# HC06_Schem.net
KiCad netlist of a schematic drawn in Altium Designer
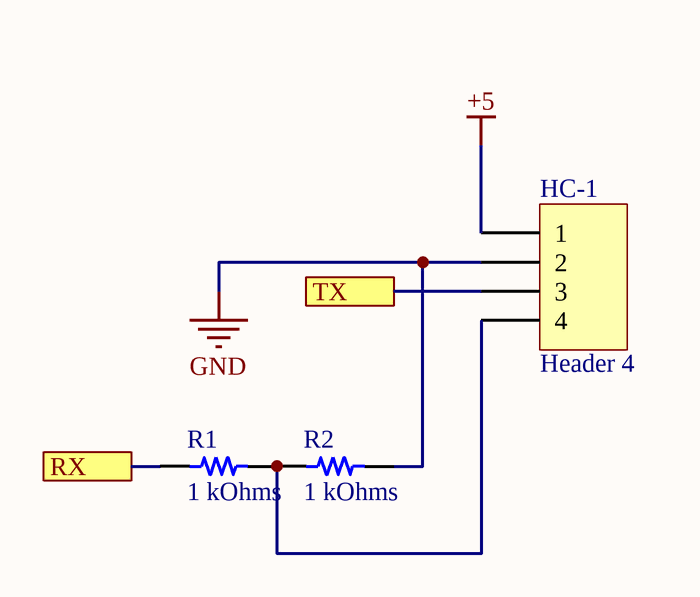
[diagram p0: HC06_Schem.SchDoc]

(export (version "E")
  (design (tool "Eeschema 10.0.6"))
  (components
    (comp (ref "HC-1")
      (value "Header 4")
      (footprint "HDR1X4")
      (description "Header, 4-Pin")
      (fields (field (name "PUBLISHER") "Altium Limited"))
      (libsource (lib "Miscellaneous Connectors") (part "Header 4"))
    )
    (comp (ref "R1")
      (value "1 kOhms")
      (footprint "RES 1210_3225")
      (description "RES SMD 1K OHM 5% 2/3W 1210")
      (fields (field (name "PART NUMBER") "ESR25JZPJ102") (field (name "MANUFACTURER") "Rohm Semiconductor"))
      (libsource (lib "Celestial Altium Library - altium_library") (part "Resistor"))
    )
    (comp (ref "R2")
      (value "1 kOhms")
      (footprint "RES 1210_3225")
      (description "RES SMD 1K OHM 5% 2/3W 1210")
      (fields (field (name "PART NUMBER") "ESR25JZPJ102") (field (name "MANUFACTURER") "Rohm Semiconductor"))
      (libsource (lib "Celestial Altium Library - altium_library") (part "Resistor"))
    )
  )
  (nets
    (net (code "1") (name "+5") (class "Default")
      (node (ref "HC-1") (pin "1") (pinfunction "1_1") (pintype "passive"))
    )
    (net (code "2") (name "/RX") (class "Default")
      (node (ref "R1") (pin "1") (pinfunction "1_1") (pintype "passive"))
    )
    (net (code "3") (name "/TX") (class "Default")
      (node (ref "HC-1") (pin "3") (pinfunction "3_3") (pintype "passive"))
    )
    (net (code "4") (name "GND") (class "Default")
      (node (ref "HC-1") (pin "2") (pinfunction "2_2") (pintype "passive"))
      (node (ref "R2") (pin "2") (pinfunction "2_2") (pintype "passive"))
    )
    (net (code "5") (name "Net-(HC-1-Pad4)") (class "Default")
      (node (ref "HC-1") (pin "4") (pinfunction "4_4") (pintype "passive"))
      (node (ref "R1") (pin "2") (pinfunction "2_2") (pintype "passive"))
      (node (ref "R2") (pin "1") (pinfunction "1_1") (pintype "passive"))
    )
  )
)
